# CANbus.net
KiCad netlist of a schematic drawn in Altium Designer
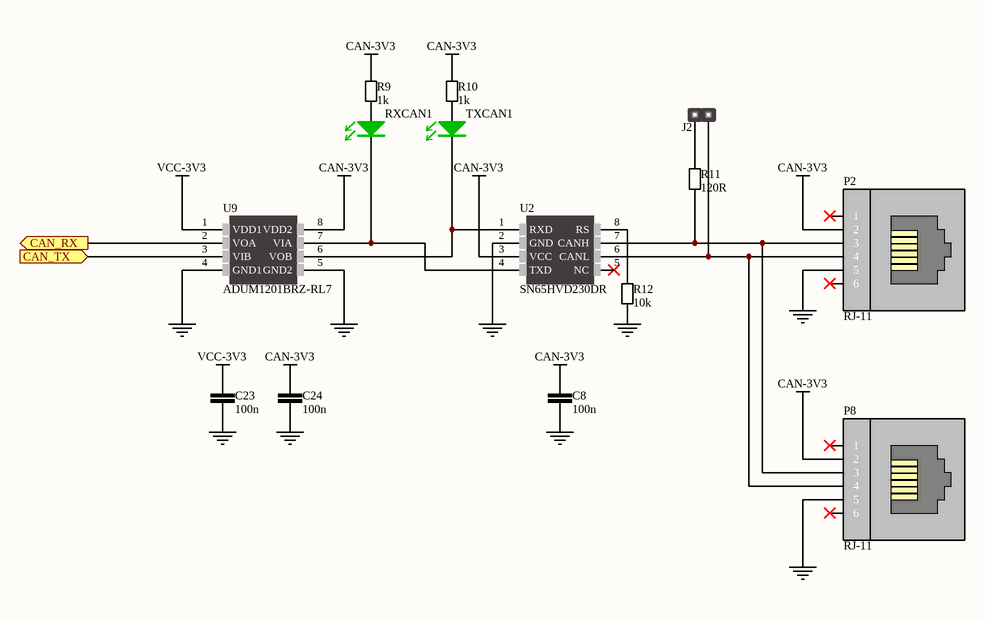
[diagram p0: CANbus.SchDoc]

(export (version "E")
  (design (tool "Eeschema 10.0.6"))
  (components
    (comp (ref "C8")
      (value "100n")
      (footprint "CER_0805")
      (description "CAP CER 100n 10V X5R 10% 0603")
      (libsource (lib "Capacitors") (part "06032105"))
    )
    (comp (ref "C23")
      (value "100n")
      (footprint "CER_0805")
      (description "CAP CER 100n 10V X5R 10% 0603")
      (libsource (lib "Capacitors") (part "06032105"))
    )
    (comp (ref "C24")
      (value "100n")
      (footprint "CER_0805")
      (description "CAP CER 100n 10V X5R 10% 0603")
      (libsource (lib "Capacitors") (part "06032105"))
    )
    (comp (ref "J2")
      (value "*")
      (footprint "HM1x2")
      (libsource (lib "Electro_Mechanical") (part "HEADER_1x2"))
    )
    (comp (ref "P2")
      (value "RJ-11")
      (footprint "RJ11-6N-B")
      (libsource (lib "Electro_Mechanical") (part "00000001"))
    )
    (comp (ref "P8")
      (value "RJ-11")
      (footprint "RJ11-6N-B")
      (description "CONN MOD JACK 6P4C R/A UNSHLD")
      (fields (field (name "MANUFACTURER PART NUMBER") "0955012641"))
      (libsource (lib "Electro_Mechanical") (part "00000001"))
    )
    (comp (ref "R9")
      (value "1k")
      (footprint "Resistors:RESC2013X38N-0805-NOOVERLAY")
      (description "RES SMD 1 kOhm 1/8W 0805")
      (fields (field (name "POWER") "0.125W, 1/8W"))
      (libsource (lib "Resistors") (part "00001001"))
    )
    (comp (ref "R10")
      (value "1k")
      (footprint "Resistors:RESC2013X38N-0805-NOOVERLAY")
      (description "RES SMD 1 kOhm 1/8W 0805")
      (fields (field (name "POWER") "0.125W, 1/8W"))
      (libsource (lib "Resistors") (part "00001001"))
    )
    (comp (ref "R11")
      (value "120R")
      (footprint "RESC2013X38N-0805-NOOVERLAY")
      (description "RES SMD 120 Ohm 1/8W 0805")
      (libsource (lib "Resistors") (part "000001200"))
    )
    (comp (ref "R12")
      (value "10k")
      (footprint "RESC2013X38N-0805-NOOVERLAY")
      (description "RES SMD 10 kOhm 1/8W 0805")
      (libsource (lib "Resistors") (part "000001002"))
    )
    (comp (ref "RXCAN1")
      (value "LED GREEN")
      (footprint "LED_GREEN_0805")
      (description "LED GREEN CLEAR 0805 SMD")
      (fields
        (field (name "MANUFACTURER") "Kingbright")
        (field (name "MANUFACTURER PART NUMBER") "APT2012SGC")
      )
      (libsource (lib "Discrete_Semiconductor") (part "LED_GREEN 0805"))
    )
    (comp (ref "TXCAN1")
      (value "LED GREEN")
      (footprint "LED_GREEN_0805")
      (description "LED GREEN CLEAR 0805 SMD")
      (fields
        (field (name "MANUFACTURER") "Kingbright")
        (field (name "MANUFACTURER PART NUMBER") "APT2012SGC")
      )
      (libsource (lib "Discrete_Semiconductor") (part "LED_GREEN 0805"))
    )
    (comp (ref "U2")
      (value "SN65HVD230DR")
      (footprint "SOIC-8")
      (description "IC EMC CAN TRANSCEIVER 8-SOIC")
      (libsource (lib "Integrated_circuits") (part "SN65HVD230"))
    )
    (comp (ref "U9")
      (value "ADUM1201BRZ-RL7")
      (footprint "SOIC-8")
      (description "DGTL ISO 2.5KV GEN PURP 8SOIC")
      (libsource (lib "Integrated_circuits") (part "ADUM1201BRZ"))
    )
  )
  (nets
    (net (code "1") (name "/CAN_RX") (class "Default")
      (node (ref "U9") (pin "2") (pinfunction "VOA_2") (pintype "passive"))
    )
    (net (code "2") (name "/CAN_TX") (class "Default")
      (node (ref "U9") (pin "3") (pinfunction "VIB_3") (pintype "passive"))
    )
    (net (code "3") (name "CAN-3V3") (class "Default")
      (node (ref "C24") (pin "2") (pinfunction "2_2") (pintype "passive"))
      (node (ref "C8") (pin "2") (pinfunction "2_2") (pintype "passive"))
      (node (ref "P2") (pin "2") (pinfunction "2_2") (pintype "passive"))
      (node (ref "P8") (pin "2") (pinfunction "2_2") (pintype "passive"))
      (node (ref "R10") (pin "2") (pinfunction "2_2") (pintype "passive"))
      (node (ref "R9") (pin "2") (pinfunction "2_2") (pintype "passive"))
      (node (ref "U2") (pin "3") (pinfunction "VCC_3") (pintype "passive"))
      (node (ref "U9") (pin "8") (pinfunction "VDD2_8") (pintype "passive"))
    )
    (net (code "4") (name "GND") (class "Default")
      (node (ref "C23") (pin "1") (pinfunction "1_1") (pintype "passive"))
      (node (ref "C24") (pin "1") (pinfunction "1_1") (pintype "passive"))
      (node (ref "C8") (pin "1") (pinfunction "1_1") (pintype "passive"))
      (node (ref "P2") (pin "5") (pinfunction "5_5") (pintype "passive"))
      (node (ref "P8") (pin "5") (pinfunction "5_5") (pintype "passive"))
      (node (ref "R12") (pin "1") (pinfunction "1_1") (pintype "passive"))
      (node (ref "U2") (pin "2") (pinfunction "GND_2") (pintype "passive"))
      (node (ref "U9") (pin "4") (pinfunction "GND1_4") (pintype "passive"))
      (node (ref "U9") (pin "5") (pinfunction "GND2_5") (pintype "passive"))
    )
    (net (code "5") (name "Net-(J2-Pad1)") (class "Default")
      (node (ref "J2") (pin "1") (pinfunction "1_1") (pintype "passive"))
      (node (ref "R11") (pin "2") (pinfunction "2_2") (pintype "passive"))
    )
    (net (code "6") (name "Net-(RXCAN1-A)") (class "Default")
      (node (ref "R9") (pin "1") (pinfunction "1_1") (pintype "passive"))
      (node (ref "RXCAN1") (pin "2") (pinfunction "A_2") (pintype "passive"))
    )
    (net (code "7") (name "Net-(RXCAN1-C)") (class "Default")
      (node (ref "RXCAN1") (pin "1") (pinfunction "C_1") (pintype "passive"))
      (node (ref "U2") (pin "4") (pinfunction "TXD_4") (pintype "passive"))
      (node (ref "U9") (pin "7") (pinfunction "VIA_7") (pintype "passive"))
    )
    (net (code "8") (name "Net-(TXCAN1-A)") (class "Default")
      (node (ref "R10") (pin "1") (pinfunction "1_1") (pintype "passive"))
      (node (ref "TXCAN1") (pin "2") (pinfunction "A_2") (pintype "passive"))
    )
    (net (code "9") (name "Net-(TXCAN1-C)") (class "Default")
      (node (ref "TXCAN1") (pin "1") (pinfunction "C_1") (pintype "passive"))
      (node (ref "U2") (pin "1") (pinfunction "RXD_1") (pintype "passive"))
      (node (ref "U9") (pin "6") (pinfunction "VOB_6") (pintype "passive"))
    )
    (net (code "10") (name "Net-(U2-CANH)") (class "Default")
      (node (ref "P2") (pin "3") (pinfunction "3_3") (pintype "passive"))
      (node (ref "P8") (pin "3") (pinfunction "3_3") (pintype "passive"))
      (node (ref "R11") (pin "1") (pinfunction "1_1") (pintype "passive"))
      (node (ref "U2") (pin "7") (pinfunction "CANH_7") (pintype "passive"))
    )
    (net (code "11") (name "Net-(U2-CANL)") (class "Default")
      (node (ref "J2") (pin "2") (pinfunction "1_2") (pintype "passive"))
      (node (ref "P2") (pin "4") (pinfunction "4_4") (pintype "passive"))
      (node (ref "P8") (pin "4") (pinfunction "4_4") (pintype "passive"))
      (node (ref "U2") (pin "6") (pinfunction "CANL_6") (pintype "passive"))
    )
    (net (code "12") (name "Net-(U2-RS)") (class "Default")
      (node (ref "R12") (pin "2") (pinfunction "2_2") (pintype "passive"))
      (node (ref "U2") (pin "8") (pinfunction "RS_8") (pintype "passive"))
    )
    (net (code "13") (name "VCC-3V3") (class "Default")
      (node (ref "C23") (pin "2") (pinfunction "2_2") (pintype "passive"))
      (node (ref "U9") (pin "1") (pinfunction "VDD1_1") (pintype "passive"))
    )
    (net (code "14") (name "unconnected-(P2-Pad1)") (class "Default")
      (node (ref "P2") (pin "1") (pinfunction "1_1") (pintype "passive+no_connect"))
    )
    (net (code "15") (name "unconnected-(P2-Pad6)") (class "Default")
      (node (ref "P2") (pin "6") (pinfunction "6_6") (pintype "passive+no_connect"))
    )
    (net (code "16") (name "unconnected-(P8-Pad1)") (class "Default")
      (node (ref "P8") (pin "1") (pinfunction "1_1") (pintype "passive+no_connect"))
    )
    (net (code "17") (name "unconnected-(P8-Pad6)") (class "Default")
      (node (ref "P8") (pin "6") (pinfunction "6_6") (pintype "passive+no_connect"))
    )
    (net (code "18") (name "unconnected-(U2-NC-Pad5)") (class "Default")
      (node (ref "U2") (pin "5") (pinfunction "NC_5") (pintype "passive+no_connect"))
    )
  )
)
